# MainProcessor.net
KiCad netlist of a schematic drawn in Altium Designer
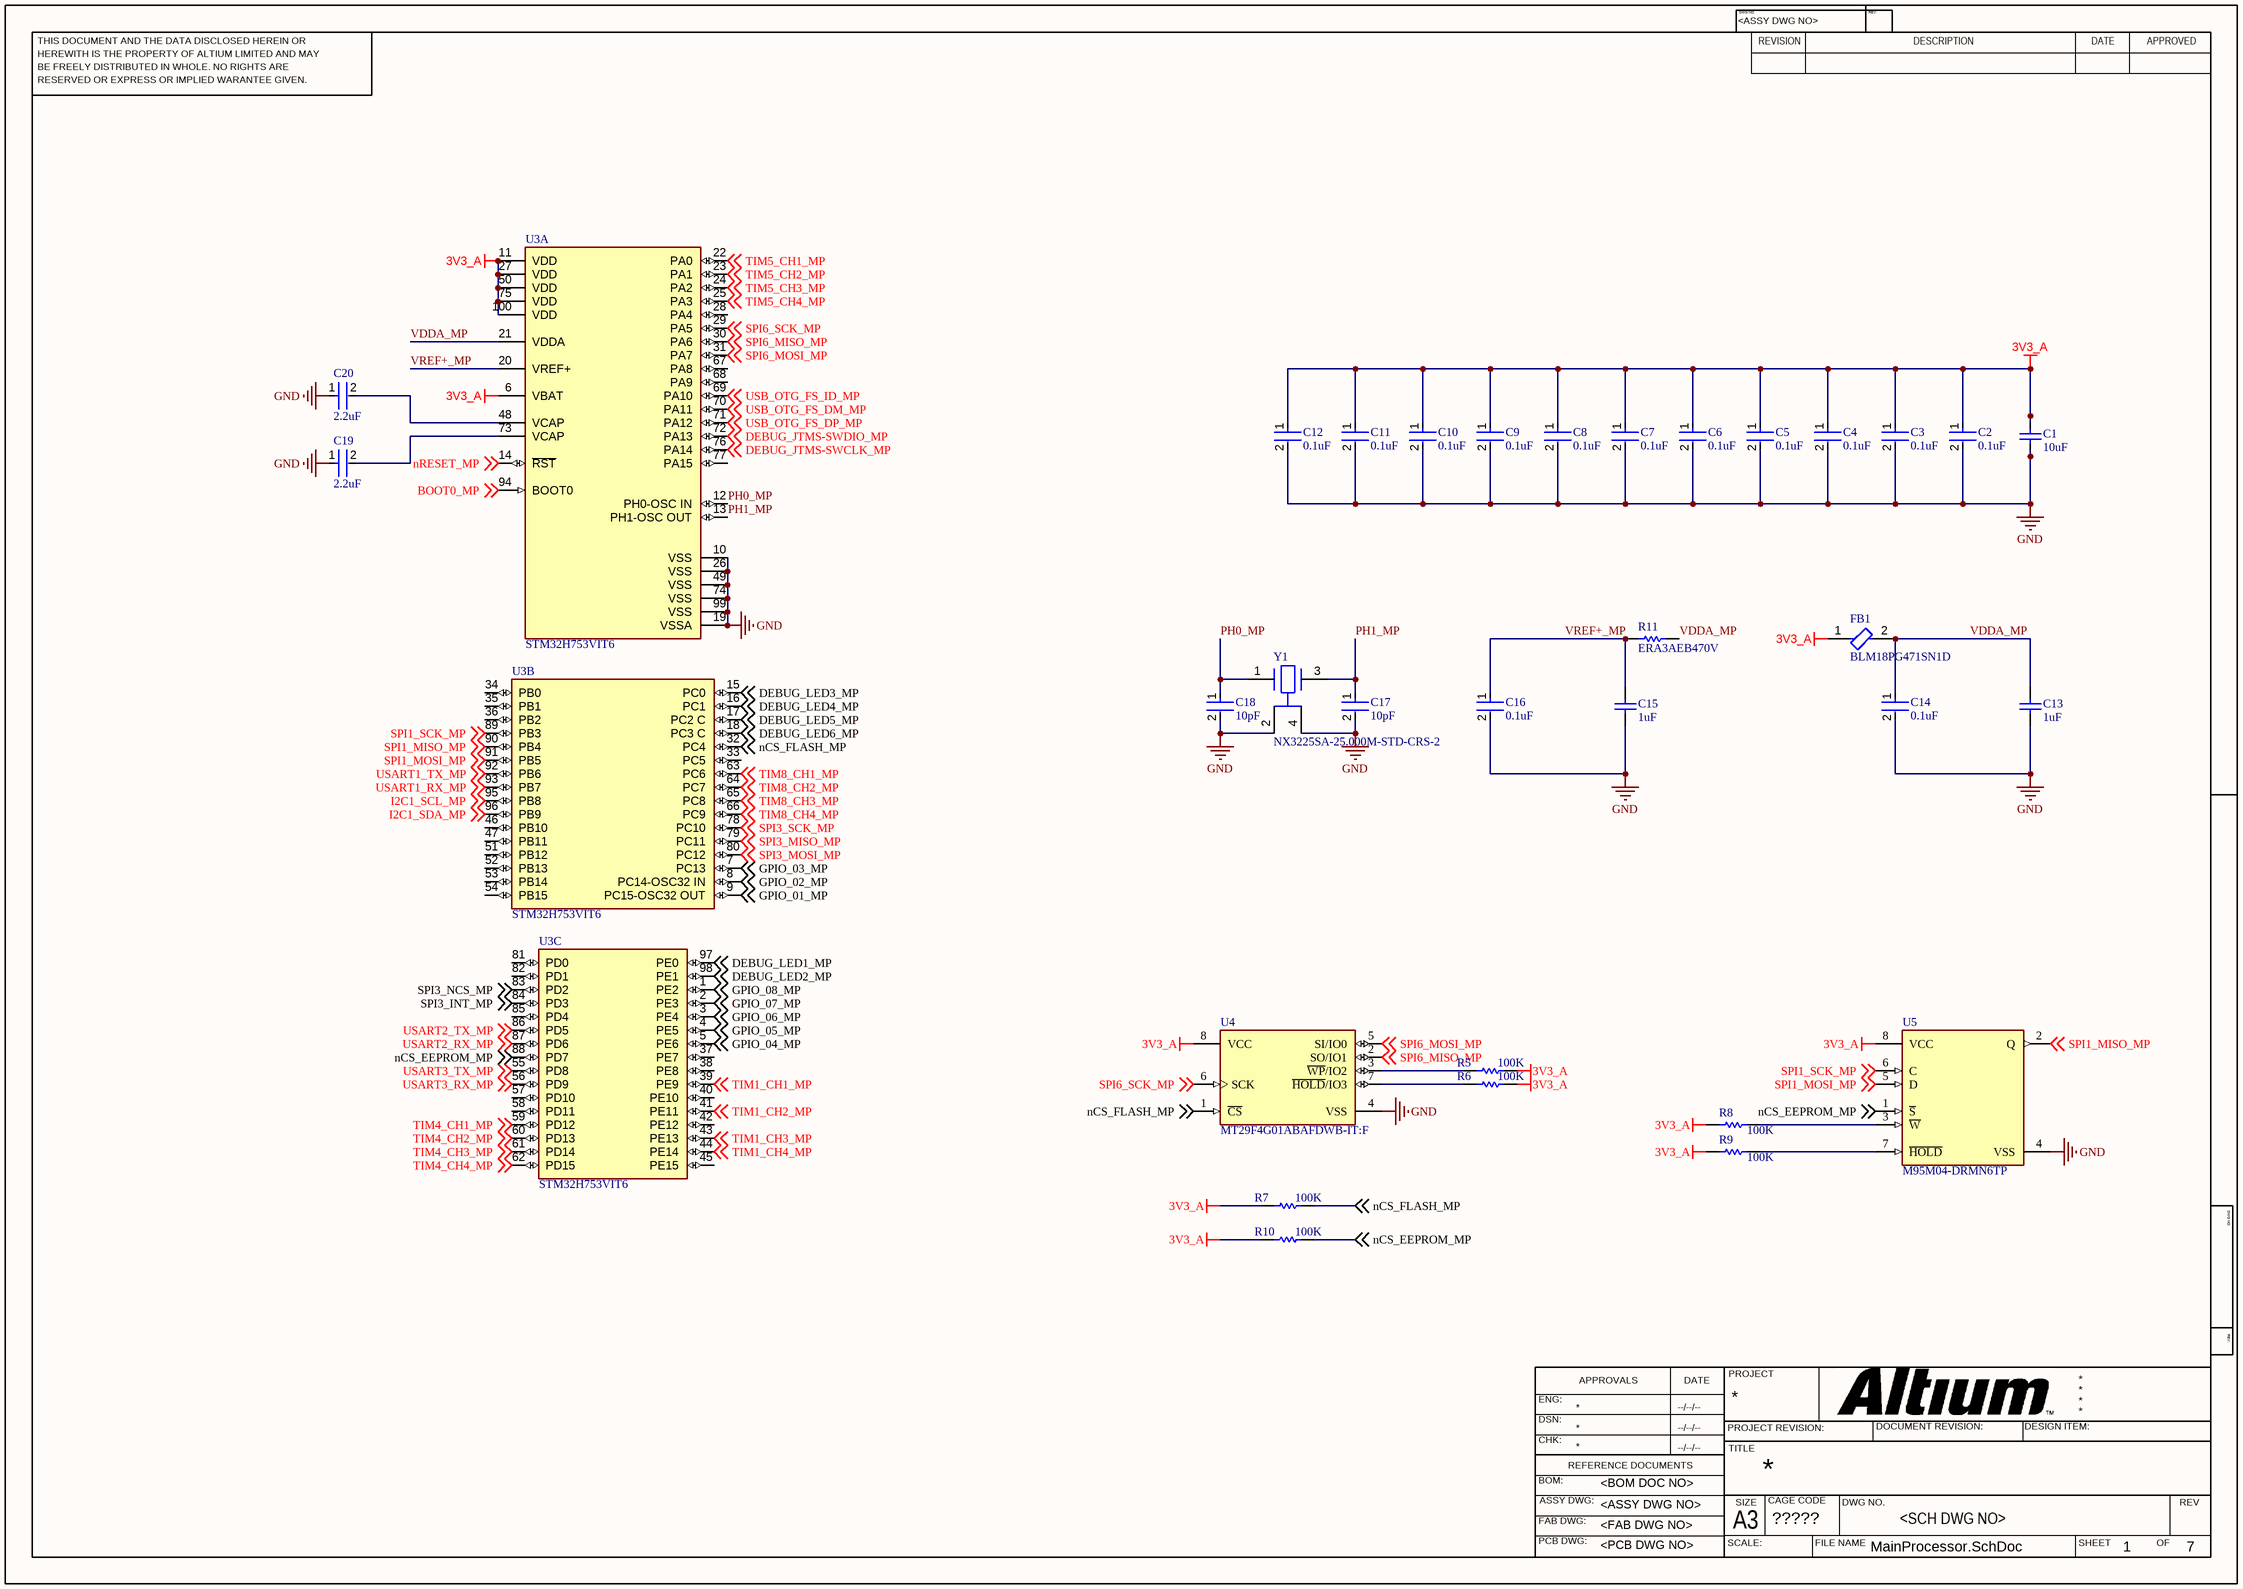
[diagram p0: MainProcessor.SchDoc]

(export (version "E")
  (design (tool "Eeschema 10.0.6"))
  (components
    (comp (ref "C1")
      (value "10uF")
      (footprint "CAPC2013X145X50LL20T25")
      (fields (field (name "MANUFACTURER") "Kemet") (field (name "PART NUMBER") "C0805C106K8RACTU"))
      (libsource (lib "Altium Content Vault") (part "CAP"))
    )
    (comp (ref "C2")
      (value "0.1uF")
      (footprint "FP-C0603C-CF-MFG")
      (description "CAP CER 0.1UF 50V X7R 0603")
      (fields (field (name "TOLERANCE") "0.1") (field (name "MANUFACTURER") "KEMET"))
      (libsource (lib "Altium Content Vault") (part "b4654b650e69147ec39a6b967a45e02"))
    )
    (comp (ref "C3")
      (value "0.1uF")
      (footprint "FP-C0603C-CF-MFG")
      (description "CAP CER 0.1UF 50V X7R 0603")
      (fields (field (name "TOLERANCE") "0.1") (field (name "MANUFACTURER") "KEMET"))
      (libsource (lib "Altium Content Vault") (part "b4654b650e69147ec39a6b967a45e02"))
    )
    (comp (ref "C4")
      (value "0.1uF")
      (footprint "FP-C0603C-CF-MFG")
      (description "CAP CER 0.1UF 50V X7R 0603")
      (fields (field (name "TOLERANCE") "0.1") (field (name "MANUFACTURER") "KEMET"))
      (libsource (lib "Altium Content Vault") (part "b4654b650e69147ec39a6b967a45e02"))
    )
    (comp (ref "C5")
      (value "0.1uF")
      (footprint "FP-C0603C-CF-MFG")
      (description "CAP CER 0.1UF 50V X7R 0603")
      (fields (field (name "TOLERANCE") "0.1") (field (name "MANUFACTURER") "KEMET"))
      (libsource (lib "Altium Content Vault") (part "b4654b650e69147ec39a6b967a45e02"))
    )
    (comp (ref "C6")
      (value "0.1uF")
      (footprint "FP-C0603C-CF-MFG")
      (description "CAP CER 0.1UF 50V X7R 0603")
      (fields (field (name "TOLERANCE") "0.1") (field (name "MANUFACTURER") "KEMET"))
      (libsource (lib "Altium Content Vault") (part "b4654b650e69147ec39a6b967a45e02"))
    )
    (comp (ref "C7")
      (value "0.1uF")
      (footprint "FP-C0603C-CF-MFG")
      (description "CAP CER 0.1UF 50V X7R 0603")
      (fields (field (name "TOLERANCE") "0.1") (field (name "MANUFACTURER") "KEMET"))
      (libsource (lib "Altium Content Vault") (part "b4654b650e69147ec39a6b967a45e02"))
    )
    (comp (ref "C8")
      (value "0.1uF")
      (footprint "FP-C0603C-CF-MFG")
      (description "CAP CER 0.1UF 50V X7R 0603")
      (fields (field (name "TOLERANCE") "0.1") (field (name "MANUFACTURER") "KEMET"))
      (libsource (lib "Altium Content Vault") (part "b4654b650e69147ec39a6b967a45e02"))
    )
    (comp (ref "C9")
      (value "0.1uF")
      (footprint "FP-C0603C-CF-MFG")
      (description "CAP CER 0.1UF 50V X7R 0603")
      (fields (field (name "TOLERANCE") "0.1") (field (name "MANUFACTURER") "KEMET"))
      (libsource (lib "Altium Content Vault") (part "b4654b650e69147ec39a6b967a45e02"))
    )
    (comp (ref "C10")
      (value "0.1uF")
      (footprint "FP-C0603C-CF-MFG")
      (description "CAP CER 0.1UF 50V X7R 0603")
      (fields (field (name "TOLERANCE") "0.1") (field (name "MANUFACTURER") "KEMET"))
      (libsource (lib "Altium Content Vault") (part "b4654b650e69147ec39a6b967a45e02"))
    )
    (comp (ref "C11")
      (value "0.1uF")
      (footprint "FP-C0603C-CF-MFG")
      (description "CAP CER 0.1UF 50V X7R 0603")
      (fields (field (name "TOLERANCE") "0.1") (field (name "MANUFACTURER") "KEMET"))
      (libsource (lib "Altium Content Vault") (part "b4654b650e69147ec39a6b967a45e02"))
    )
    (comp (ref "C12")
      (value "0.1uF")
      (footprint "FP-C0603C-CF-MFG")
      (description "CAP CER 0.1UF 50V X7R 0603")
      (fields (field (name "TOLERANCE") "0.1") (field (name "MANUFACTURER") "KEMET"))
      (libsource (lib "Altium Content Vault") (part "b4654b650e69147ec39a6b967a45e02"))
    )
    (comp (ref "C13")
      (value "1uF")
      (footprint "CAPC1608X90X35LL15T15")
      (fields (field (name "MANUFACTURER") "Kemet") (field (name "PART NUMBER") "C0603C105K4RACTU"))
      (libsource (lib "Altium Content Vault") (part "CAP"))
    )
    (comp (ref "C14")
      (value "0.1uF")
      (footprint "FP-C0603C-CF-MFG")
      (description "CAP CER 0.1UF 50V X7R 0603")
      (fields (field (name "TOLERANCE") "0.1") (field (name "MANUFACTURER") "KEMET"))
      (libsource (lib "Altium Content Vault") (part "b4654b650e69147ec39a6b967a45e02"))
    )
    (comp (ref "C15")
      (value "1uF")
      (footprint "CAPC1608X90X35LL15T15")
      (fields (field (name "MANUFACTURER") "Kemet") (field (name "PART NUMBER") "C0603C105K4RACTU"))
      (libsource (lib "Altium Content Vault") (part "CAP"))
    )
    (comp (ref "C16")
      (value "0.1uF")
      (footprint "FP-C0603C-CF-MFG")
      (description "CAP CER 0.1UF 50V X7R 0603")
      (fields (field (name "TOLERANCE") "0.1") (field (name "MANUFACTURER") "KEMET"))
      (libsource (lib "Altium Content Vault") (part "b4654b650e69147ec39a6b967a45e02"))
    )
    (comp (ref "C17")
      (value "10pF")
      (footprint "FP-C0603C-CF-MFG")
      (description "CAP CER 10PF 50V NP0 0603")
      (fields (field (name "MANUFACTURER") "KEMET") (field (name "TOLERANCE") "0.25 pF"))
      (libsource (lib "Altium Content Vault") (part "b4654b650e69147ec39a6b967a45e02"))
    )
    (comp (ref "C18")
      (value "10pF")
      (footprint "FP-C0603C-CF-MFG")
      (description "CAP CER 10PF 50V NP0 0603")
      (fields (field (name "MANUFACTURER") "KEMET") (field (name "TOLERANCE") "0.25 pF"))
      (libsource (lib "Altium Content Vault") (part "b4654b650e69147ec39a6b967a45e02"))
    )
    (comp (ref "C19")
      (value "2.2uF")
      (footprint "FP-GRM188-0_1-e0_2_0_5-MFG")
      (description "Chip Multilayer Ceramic Capacitors for General Purpose, 0603, 2.2uF, X7R, 15%, 10%, 10V")
      (fields (field (name "VOLTAGE") "10V") (field (name "TOLERANCE") "10%"))
      (libsource (lib "Altium Content Vault") (part "11868f565c42a9108669ba33697ecf6"))
    )
    (comp (ref "C20")
      (value "2.2uF")
      (footprint "FP-GRM188-0_1-e0_2_0_5-MFG")
      (description "Chip Multilayer Ceramic Capacitors for General Purpose, 0603, 2.2uF, X7R, 15%, 10%, 10V")
      (fields (field (name "VOLTAGE") "10V") (field (name "TOLERANCE") "10%"))
      (libsource (lib "Altium Content Vault") (part "11868f565c42a9108669ba33697ecf6"))
    )
    (comp (ref "FB1")
      (value "BLM18PG471SN1D")
      (footprint "FP-BLM18-0_15-t0_8-MFG")
      (description "Chip Ferrite Bead, 0603, 470Ω @ 100MHz, 0.2Ω, 25%, 1A")
      (fields (field (name "TOLERANCE") "25%"))
      (libsource (lib "Altium Content Vault") (part "5f30dd21d616792df468990f7003faa"))
    )
    (comp (ref "R5")
      (value "100K")
      (footprint "RESC1608X55X30ML20T10")
      (fields (field (name "PART NUMBER") "RK73B1JTTD104J") (field (name "MANUFACTURER") "KOA Speer"))
      (libsource (lib "Altium Content Vault") (part "RES"))
    )
    (comp (ref "R6")
      (value "100K")
      (footprint "RESC1608X55X30ML20T10")
      (fields (field (name "PART NUMBER") "RK73B1JTTD104J") (field (name "MANUFACTURER") "KOA Speer"))
      (libsource (lib "Altium Content Vault") (part "RES"))
    )
    (comp (ref "R7")
      (value "100K")
      (footprint "RESC1608X55X30ML20T10")
      (fields (field (name "PART NUMBER") "RK73B1JTTD104J") (field (name "MANUFACTURER") "KOA Speer"))
      (libsource (lib "Altium Content Vault") (part "RES"))
    )
    (comp (ref "R8")
      (value "100K")
      (footprint "RESC1608X55X30ML20T10")
      (fields (field (name "PART NUMBER") "RK73B1JTTD104J") (field (name "MANUFACTURER") "KOA Speer"))
      (libsource (lib "Altium Content Vault") (part "RES"))
    )
    (comp (ref "R9")
      (value "100K")
      (footprint "RESC1608X55X30ML20T10")
      (fields (field (name "PART NUMBER") "RK73B1JTTD104J") (field (name "MANUFACTURER") "KOA Speer"))
      (libsource (lib "Altium Content Vault") (part "RES"))
    )
    (comp (ref "R10")
      (value "100K")
      (footprint "RESC1608X55X30ML20T10")
      (fields (field (name "PART NUMBER") "RK73B1JTTD104J") (field (name "MANUFACTURER") "KOA Speer"))
      (libsource (lib "Altium Content Vault") (part "RES"))
    )
    (comp (ref "R11")
      (value "ERA3AEB470V")
      (footprint "RESC1608X55X30NL20T20")
      (fields (field (name "MANUFACTURER") "Panasonic"))
      (libsource (lib "Altium Content Vault") (part "RES"))
    )
    (comp (ref "U3")
      (value "STM32H753VIT6")
      (footprint "FP-LQFP100-1L-MFG")
      (description "LQFP 100 14X14X1.4")
      (fields
        (field (name "OCTOPART") "https://octopart.com/stm32h753vit6-stmicroelectronics-87879769")
        (field (name "MANUFACTURER") "STMicroelectronics")
      )
      (libsource (lib "Altium Content Vault") (part "0d804454ec25a714beb1806164230ed"))
    )
    (comp (ref "U4")
      (value "MT29F4G01ABAFDWB-IT:F")
      (footprint "FP-WB-IPC_B")
      (description "IC FLASH 4GBIT SPI UPDFN")
      (libsource (lib "Altium Content Vault") (part "2a22d8121842150c115fe802c55be1a"))
    )
    (comp (ref "U5")
      (value "M95M04-DRMN6TP")
      (footprint "FP-SO8N-SO-A-IPC_C")
      (description "STANDARD SERIAL EEPROM")
      (libsource (lib "Altium Content Vault") (part "c55af301368cfa6937ebbf8cb00c05d"))
    )
    (comp (ref "Y1")
      (value "NX3225SA-25.000M-STD-CRS-2")
      (footprint "FP-NX3225SA-MFG")
      (description "CRYSTAL 25.0000MHZ 8PF SMD")
      (fields
        (field (name "OCTOPART") "https://octopart.com/nx3225sa-25.000m-std-crs-2-ndk-51374293")
        (field (name "MANUFACTURER") "NDK")
      )
      (libsource (lib "Altium Content Vault") (part "2e6e5a9c86ccbddb5e6335a7c0ff6ff"))
    )
  )
  (nets
    (net (code "1") (name "/PH0_MP") (class "Default")
      (node (ref "C18") (pin "1") (pinfunction "1_1") (pintype "passive"))
      (node (ref "U3") (pin "12") (pinfunction "PH0-OSC_IN_12") (pintype "bidirectional"))
      (node (ref "Y1") (pin "1") (pinfunction "1_1") (pintype "passive"))
    )
    (net (code "2") (name "/PH1_MP") (class "Default")
      (node (ref "C17") (pin "1") (pinfunction "1_1") (pintype "passive"))
      (node (ref "U3") (pin "13") (pinfunction "PH1-OSC_OUT_13") (pintype "bidirectional"))
      (node (ref "Y1") (pin "3") (pinfunction "3_3") (pintype "passive"))
    )
    (net (code "3") (name "/VDDA_MP") (class "Default")
      (node (ref "C13") (pin "1") (pinfunction "1_1") (pintype "passive"))
      (node (ref "C14") (pin "1") (pinfunction "1_1") (pintype "passive"))
      (node (ref "FB1") (pin "2") (pinfunction "2_2") (pintype "passive"))
      (node (ref "R11") (pin "2") (pinfunction "2_2") (pintype "passive"))
      (node (ref "U3") (pin "21") (pinfunction "VDDA_21") (pintype "power_in"))
    )
    (net (code "4") (name "/VREF+_MP") (class "Default")
      (node (ref "C15") (pin "1") (pinfunction "1_1") (pintype "passive"))
      (node (ref "C16") (pin "1") (pinfunction "1_1") (pintype "passive"))
      (node (ref "R11") (pin "1") (pinfunction "1_1") (pintype "passive"))
      (node (ref "U3") (pin "20") (pinfunction "VREF+_20") (pintype "power_in"))
    )
    (net (code "5") (name "3V3_A") (class "Default")
      (node (ref "C1") (pin "1") (pinfunction "1_1") (pintype "passive"))
      (node (ref "C10") (pin "1") (pinfunction "1_1") (pintype "passive"))
      (node (ref "C11") (pin "1") (pinfunction "1_1") (pintype "passive"))
      (node (ref "C12") (pin "1") (pinfunction "1_1") (pintype "passive"))
      (node (ref "C2") (pin "1") (pinfunction "1_1") (pintype "passive"))
      (node (ref "C3") (pin "1") (pinfunction "1_1") (pintype "passive"))
      (node (ref "C4") (pin "1") (pinfunction "1_1") (pintype "passive"))
      (node (ref "C5") (pin "1") (pinfunction "1_1") (pintype "passive"))
      (node (ref "C6") (pin "1") (pinfunction "1_1") (pintype "passive"))
      (node (ref "C7") (pin "1") (pinfunction "1_1") (pintype "passive"))
      (node (ref "C8") (pin "1") (pinfunction "1_1") (pintype "passive"))
      (node (ref "C9") (pin "1") (pinfunction "1_1") (pintype "passive"))
      (node (ref "FB1") (pin "1") (pinfunction "1_1") (pintype "passive"))
      (node (ref "R10") (pin "2") (pinfunction "2_2") (pintype "passive"))
      (node (ref "R5") (pin "2") (pinfunction "2_2") (pintype "passive"))
      (node (ref "R6") (pin "2") (pinfunction "2_2") (pintype "passive"))
      (node (ref "R7") (pin "2") (pinfunction "2_2") (pintype "passive"))
      (node (ref "R8") (pin "2") (pinfunction "2_2") (pintype "passive"))
      (node (ref "R9") (pin "2") (pinfunction "2_2") (pintype "passive"))
      (node (ref "U3") (pin "100") (pinfunction "VDD_100") (pintype "power_in"))
      (node (ref "U3") (pin "11") (pinfunction "VDD_11") (pintype "power_in"))
      (node (ref "U3") (pin "27") (pinfunction "VDD_27") (pintype "power_in"))
      (node (ref "U3") (pin "50") (pinfunction "VDD_50") (pintype "power_in"))
      (node (ref "U3") (pin "6") (pinfunction "VBAT_6") (pintype "power_in"))
      (node (ref "U3") (pin "75") (pinfunction "VDD_75") (pintype "power_in"))
      (node (ref "U4") (pin "8") (pinfunction "VCC_8") (pintype "power_in"))
      (node (ref "U5") (pin "8") (pinfunction "VCC_8") (pintype "power_in"))
    )
    (net (code "6") (name "BOOT0_MP") (class "Default")
      (node (ref "U3") (pin "94") (pinfunction "BOOT0_94") (pintype "input"))
    )
    (net (code "7") (name "DEBUG_JTMS-SWCLK_MP") (class "Default")
      (node (ref "U3") (pin "76") (pinfunction "PA14_76") (pintype "bidirectional"))
    )
    (net (code "8") (name "DEBUG_JTMS-SWDIO_MP") (class "Default")
      (node (ref "U3") (pin "72") (pinfunction "PA13_72") (pintype "bidirectional"))
    )
    (net (code "9") (name "DEBUG_LED1_MP") (class "Default")
      (node (ref "U3") (pin "97") (pinfunction "PE0_97") (pintype "bidirectional"))
    )
    (net (code "10") (name "DEBUG_LED2_MP") (class "Default")
      (node (ref "U3") (pin "98") (pinfunction "PE1_98") (pintype "bidirectional"))
    )
    (net (code "11") (name "DEBUG_LED3_MP") (class "Default")
      (node (ref "U3") (pin "15") (pinfunction "PC0_15") (pintype "bidirectional"))
    )
    (net (code "12") (name "DEBUG_LED4_MP") (class "Default")
      (node (ref "U3") (pin "16") (pinfunction "PC1_16") (pintype "bidirectional"))
    )
    (net (code "13") (name "DEBUG_LED5_MP") (class "Default")
      (node (ref "U3") (pin "17") (pinfunction "PC2_C_17") (pintype "bidirectional"))
    )
    (net (code "14") (name "DEBUG_LED6_MP") (class "Default")
      (node (ref "U3") (pin "18") (pinfunction "PC3_C_18") (pintype "bidirectional"))
    )
    (net (code "15") (name "GND") (class "Default")
      (node (ref "C1") (pin "2") (pinfunction "2_2") (pintype "passive"))
      (node (ref "C10") (pin "2") (pinfunction "2_2") (pintype "passive"))
      (node (ref "C11") (pin "2") (pinfunction "2_2") (pintype "passive"))
      (node (ref "C12") (pin "2") (pinfunction "2_2") (pintype "passive"))
      (node (ref "C13") (pin "2") (pinfunction "2_2") (pintype "passive"))
      (node (ref "C14") (pin "2") (pinfunction "2_2") (pintype "passive"))
      (node (ref "C15") (pin "2") (pinfunction "2_2") (pintype "passive"))
      (node (ref "C16") (pin "2") (pinfunction "2_2") (pintype "passive"))
      (node (ref "C17") (pin "2") (pinfunction "2_2") (pintype "passive"))
      (node (ref "C18") (pin "2") (pinfunction "2_2") (pintype "passive"))
      (node (ref "C19") (pin "1") (pinfunction "1_1") (pintype "passive"))
      (node (ref "C2") (pin "2") (pinfunction "2_2") (pintype "passive"))
      (node (ref "C20") (pin "1") (pinfunction "1_1") (pintype "passive"))
      (node (ref "C3") (pin "2") (pinfunction "2_2") (pintype "passive"))
      (node (ref "C4") (pin "2") (pinfunction "2_2") (pintype "passive"))
      (node (ref "C5") (pin "2") (pinfunction "2_2") (pintype "passive"))
      (node (ref "C6") (pin "2") (pinfunction "2_2") (pintype "passive"))
      (node (ref "C7") (pin "2") (pinfunction "2_2") (pintype "passive"))
      (node (ref "C8") (pin "2") (pinfunction "2_2") (pintype "passive"))
      (node (ref "C9") (pin "2") (pinfunction "2_2") (pintype "passive"))
      (node (ref "U3") (pin "10") (pinfunction "VSS_10") (pintype "power_in"))
      (node (ref "U3") (pin "19") (pinfunction "VSSA_19") (pintype "power_in"))
      (node (ref "U3") (pin "26") (pinfunction "VSS_26") (pintype "power_in"))
      (node (ref "U3") (pin "49") (pinfunction "VSS_49") (pintype "power_in"))
      (node (ref "U3") (pin "74") (pinfunction "VSS_74") (pintype "power_in"))
      (node (ref "U3") (pin "99") (pinfunction "VSS_99") (pintype "power_in"))
      (node (ref "U4") (pin "4") (pinfunction "VSS_4") (pintype "power_in"))
      (node (ref "U5") (pin "4") (pinfunction "VSS_4") (pintype "power_in"))
      (node (ref "Y1") (pin "2") (pinfunction "GND_2") (pintype "power_in"))
      (node (ref "Y1") (pin "4") (pinfunction "GND_4") (pintype "power_in"))
    )
    (net (code "16") (name "GPIO_01_MP") (class "Default")
      (node (ref "U3") (pin "9") (pinfunction "PC15-OSC32_OUT_9") (pintype "bidirectional"))
    )
    (net (code "17") (name "GPIO_02_MP") (class "Default")
      (node (ref "U3") (pin "8") (pinfunction "PC14-OSC32_IN_8") (pintype "bidirectional"))
    )
    (net (code "18") (name "GPIO_03_MP") (class "Default")
      (node (ref "U3") (pin "7") (pinfunction "PC13_7") (pintype "bidirectional"))
    )
    (net (code "19") (name "GPIO_04_MP") (class "Default")
      (node (ref "U3") (pin "5") (pinfunction "PE6_5") (pintype "bidirectional"))
    )
    (net (code "20") (name "GPIO_05_MP") (class "Default")
      (node (ref "U3") (pin "4") (pinfunction "PE5_4") (pintype "bidirectional"))
    )
    (net (code "21") (name "GPIO_06_MP") (class "Default")
      (node (ref "U3") (pin "3") (pinfunction "PE4_3") (pintype "bidirectional"))
    )
    (net (code "22") (name "GPIO_07_MP") (class "Default")
      (node (ref "U3") (pin "2") (pinfunction "PE3_2") (pintype "bidirectional"))
    )
    (net (code "23") (name "GPIO_08_MP") (class "Default")
      (node (ref "U3") (pin "1") (pinfunction "PE2_1") (pintype "bidirectional"))
    )
    (net (code "24") (name "I2C1_SCL_MP") (class "Default")
      (node (ref "U3") (pin "95") (pinfunction "PB8_95") (pintype "bidirectional"))
    )
    (net (code "25") (name "I2C1_SDA_MP") (class "Default")
      (node (ref "U3") (pin "96") (pinfunction "PB9_96") (pintype "bidirectional"))
    )
    (net (code "26") (name "Net-(C19-Pad2)") (class "Default")
      (node (ref "C19") (pin "2") (pinfunction "2_2") (pintype "passive"))
      (node (ref "U3") (pin "73") (pinfunction "VCAP_73") (pintype "power_in"))
    )
    (net (code "27") (name "Net-(C20-Pad2)") (class "Default")
      (node (ref "C20") (pin "2") (pinfunction "2_2") (pintype "passive"))
      (node (ref "U3") (pin "48") (pinfunction "VCAP_48") (pintype "power_in"))
    )
    (net (code "28") (name "Net-(U4-~{HOLD}{slash}IO3)") (class "Default")
      (node (ref "R6") (pin "1") (pinfunction "1_1") (pintype "passive"))
      (node (ref "U4") (pin "7") (pinfunction "~{HOLD}/IO3_7") (pintype "bidirectional"))
    )
    (net (code "29") (name "Net-(U4-~{WP}{slash}IO2)") (class "Default")
      (node (ref "R5") (pin "1") (pinfunction "1_1") (pintype "passive"))
      (node (ref "U4") (pin "3") (pinfunction "~{WP}/IO2_3") (pintype "bidirectional"))
    )
    (net (code "30") (name "Net-(U5-~{HOLD})") (class "Default")
      (node (ref "R9") (pin "1") (pinfunction "1_1") (pintype "passive"))
      (node (ref "U5") (pin "7") (pinfunction "~{HOLD}_7") (pintype "input"))
    )
    (net (code "31") (name "Net-(U5-~{W})") (class "Default")
      (node (ref "R8") (pin "1") (pinfunction "1_1") (pintype "passive"))
      (node (ref "U5") (pin "3") (pinfunction "~{W}_3") (pintype "input"))
    )
    (net (code "32") (name "SPI1_MISO_MP") (class "Default")
      (node (ref "U3") (pin "90") (pinfunction "PB4_90") (pintype "bidirectional"))
      (node (ref "U5") (pin "2") (pinfunction "Q_2") (pintype "output"))
    )
    (net (code "33") (name "SPI1_MOSI_MP") (class "Default")
      (node (ref "U3") (pin "91") (pinfunction "PB5_91") (pintype "bidirectional"))
      (node (ref "U5") (pin "5") (pinfunction "D_5") (pintype "input"))
    )
    (net (code "34") (name "SPI1_SCK_MP") (class "Default")
      (node (ref "U3") (pin "89") (pinfunction "PB3_89") (pintype "bidirectional"))
      (node (ref "U5") (pin "6") (pinfunction "C_6") (pintype "input"))
    )
    (net (code "35") (name "SPI3_INT_MP") (class "Default")
      (node (ref "U3") (pin "84") (pinfunction "PD3_84") (pintype "bidirectional"))
    )
    (net (code "36") (name "SPI3_MISO_MP") (class "Default")
      (node (ref "U3") (pin "79") (pinfunction "PC11_79") (pintype "bidirectional"))
    )
    (net (code "37") (name "SPI3_MOSI_MP") (class "Default")
      (node (ref "U3") (pin "80") (pinfunction "PC12_80") (pintype "bidirectional"))
    )
    (net (code "38") (name "SPI3_NCS_MP") (class "Default")
      (node (ref "U3") (pin "83") (pinfunction "PD2_83") (pintype "bidirectional"))
    )
    (net (code "39") (name "SPI3_SCK_MP") (class "Default")
      (node (ref "U3") (pin "78") (pinfunction "PC10_78") (pintype "bidirectional"))
    )
    (net (code "40") (name "SPI6_MISO_MP") (class "Default")
      (node (ref "U3") (pin "30") (pinfunction "PA6_30") (pintype "bidirectional"))
      (node (ref "U4") (pin "2") (pinfunction "SO/IO1_2") (pintype "bidirectional"))
    )
    (net (code "41") (name "SPI6_MOSI_MP") (class "Default")
      (node (ref "U3") (pin "31") (pinfunction "PA7_31") (pintype "bidirectional"))
      (node (ref "U4") (pin "5") (pinfunction "SI/IO0_5") (pintype "bidirectional"))
    )
    (net (code "42") (name "SPI6_SCK_MP") (class "Default")
      (node (ref "U3") (pin "29") (pinfunction "PA5_29") (pintype "bidirectional"))
      (node (ref "U4") (pin "6") (pinfunction "SCK_6") (pintype "input"))
    )
    (net (code "43") (name "TIM1_CH1_MP") (class "Default")
      (node (ref "U3") (pin "39") (pinfunction "PE9_39") (pintype "bidirectional"))
    )
    (net (code "44") (name "TIM1_CH2_MP") (class "Default")
      (node (ref "U3") (pin "41") (pinfunction "PE11_41") (pintype "bidirectional"))
    )
    (net (code "45") (name "TIM1_CH3_MP") (class "Default")
      (node (ref "U3") (pin "43") (pinfunction "PE13_43") (pintype "bidirectional"))
    )
    (net (code "46") (name "TIM1_CH4_MP") (class "Default")
      (node (ref "U3") (pin "44") (pinfunction "PE14_44") (pintype "bidirectional"))
    )
    (net (code "47") (name "TIM4_CH1_MP") (class "Default")
      (node (ref "U3") (pin "59") (pinfunction "PD12_59") (pintype "bidirectional"))
    )
    (net (code "48") (name "TIM4_CH2_MP") (class "Default")
      (node (ref "U3") (pin "60") (pinfunction "PD13_60") (pintype "bidirectional"))
    )
    (net (code "49") (name "TIM4_CH3_MP") (class "Default")
      (node (ref "U3") (pin "61") (pinfunction "PD14_61") (pintype "bidirectional"))
    )
    (net (code "50") (name "TIM4_CH4_MP") (class "Default")
      (node (ref "U3") (pin "62") (pinfunction "PD15_62") (pintype "bidirectional"))
    )
    (net (code "51") (name "TIM5_CH1_MP") (class "Default")
      (node (ref "U3") (pin "22") (pinfunction "PA0_22") (pintype "bidirectional"))
    )
    (net (code "52") (name "TIM5_CH2_MP") (class "Default")
      (node (ref "U3") (pin "23") (pinfunction "PA1_23") (pintype "bidirectional"))
    )
    (net (code "53") (name "TIM5_CH3_MP") (class "Default")
      (node (ref "U3") (pin "24") (pinfunction "PA2_24") (pintype "bidirectional"))
    )
    (net (code "54") (name "TIM5_CH4_MP") (class "Default")
      (node (ref "U3") (pin "25") (pinfunction "PA3_25") (pintype "bidirectional"))
    )
    (net (code "55") (name "TIM8_CH1_MP") (class "Default")
      (node (ref "U3") (pin "63") (pinfunction "PC6_63") (pintype "bidirectional"))
    )
    (net (code "56") (name "TIM8_CH2_MP") (class "Default")
      (node (ref "U3") (pin "64") (pinfunction "PC7_64") (pintype "bidirectional"))
    )
    (net (code "57") (name "TIM8_CH3_MP") (class "Default")
      (node (ref "U3") (pin "65") (pinfunction "PC8_65") (pintype "bidirectional"))
    )
    (net (code "58") (name "TIM8_CH4_MP") (class "Default")
      (node (ref "U3") (pin "66") (pinfunction "PC9_66") (pintype "bidirectional"))
    )
    (net (code "59") (name "USART1_RX_MP") (class "Default")
      (node (ref "U3") (pin "93") (pinfunction "PB7_93") (pintype "bidirectional"))
    )
    (net (code "60") (name "USART1_TX_MP") (class "Default")
      (node (ref "U3") (pin "92") (pinfunction "PB6_92") (pintype "bidirectional"))
    )
    (net (code "61") (name "USART2_RX_MP") (class "Default")
      (node (ref "U3") (pin "87") (pinfunction "PD6_87") (pintype "bidirectional"))
    )
    (net (code "62") (name "USART2_TX_MP") (class "Default")
      (node (ref "U3") (pin "86") (pinfunction "PD5_86") (pintype "bidirectional"))
    )
    (net (code "63") (name "USART3_RX_MP") (class "Default")
      (node (ref "U3") (pin "56") (pinfunction "PD9_56") (pintype "bidirectional"))
    )
    (net (code "64") (name "USART3_TX_MP") (class "Default")
      (node (ref "U3") (pin "55") (pinfunction "PD8_55") (pintype "bidirectional"))
    )
    (net (code "65") (name "USB_OTG_FS_DM_MP") (class "Default")
      (node (ref "U3") (pin "70") (pinfunction "PA11_70") (pintype "bidirectional"))
    )
    (net (code "66") (name "USB_OTG_FS_DP_MP") (class "Default")
      (node (ref "U3") (pin "71") (pinfunction "PA12_71") (pintype "bidirectional"))
    )
    (net (code "67") (name "USB_OTG_FS_ID_MP") (class "Default")
      (node (ref "U3") (pin "69") (pinfunction "PA10_69") (pintype "bidirectional"))
    )
    (net (code "68") (name "nCS_EEPROM_MP") (class "Default")
      (node (ref "R10") (pin "1") (pinfunction "1_1") (pintype "passive"))
      (node (ref "U3") (pin "88") (pinfunction "PD7_88") (pintype "bidirectional"))
      (node (ref "U5") (pin "1") (pinfunction "~{S}_1") (pintype "input"))
    )
    (net (code "69") (name "nCS_FLASH_MP") (class "Default")
      (node (ref "R7") (pin "1") (pinfunction "1_1") (pintype "passive"))
      (node (ref "U3") (pin "32") (pinfunction "PC4_32") (pintype "bidirectional"))
      (node (ref "U4") (pin "1") (pinfunction "~{CS}_1") (pintype "input"))
    )
    (net (code "70") (name "nRESET_MP") (class "Default")
      (node (ref "U3") (pin "14") (pinfunction "~{RST}_14") (pintype "bidirectional"))
    )
    (net (code "71") (name "unconnected-(U3A-PA4-Pad28)") (class "Default")
      (node (ref "U3") (pin "28") (pinfunction "PA4_28") (pintype "bidirectional"))
    )
    (net (code "72") (name "unconnected-(U3A-PA8-Pad67)") (class "Default")
      (node (ref "U3") (pin "67") (pinfunction "PA8_67") (pintype "bidirectional"))
    )
    (net (code "73") (name "unconnected-(U3A-PA9-Pad68)") (class "Default")
      (node (ref "U3") (pin "68") (pinfunction "PA9_68") (pintype "bidirectional"))
    )
    (net (code "74") (name "unconnected-(U3A-PA15-Pad77)") (class "Default")
      (node (ref "U3") (pin "77") (pinfunction "PA15_77") (pintype "bidirectional"))
    )
    (net (code "75") (name "unconnected-(U3B-PB0-Pad34)") (class "Default")
      (node (ref "U3") (pin "34") (pinfunction "PB0_34") (pintype "bidirectional"))
    )
    (net (code "76") (name "unconnected-(U3B-PB1-Pad35)") (class "Default")
      (node (ref "U3") (pin "35") (pinfunction "PB1_35") (pintype "bidirectional"))
    )
    (net (code "77") (name "unconnected-(U3B-PB2-Pad36)") (class "Default")
      (node (ref "U3") (pin "36") (pinfunction "PB2_36") (pintype "bidirectional"))
    )
    (net (code "78") (name "unconnected-(U3B-PB10-Pad46)") (class "Default")
      (node (ref "U3") (pin "46") (pinfunction "PB10_46") (pintype "bidirectional"))
    )
    (net (code "79") (name "unconnected-(U3B-PB11-Pad47)") (class "Default")
      (node (ref "U3") (pin "47") (pinfunction "PB11_47") (pintype "bidirectional"))
    )
    (net (code "80") (name "unconnected-(U3B-PB12-Pad51)") (class "Default")
      (node (ref "U3") (pin "51") (pinfunction "PB12_51") (pintype "bidirectional"))
    )
    (net (code "81") (name "unconnected-(U3B-PB13-Pad52)") (class "Default")
      (node (ref "U3") (pin "52") (pinfunction "PB13_52") (pintype "bidirectional"))
    )
    (net (code "82") (name "unconnected-(U3B-PB14-Pad53)") (class "Default")
      (node (ref "U3") (pin "53") (pinfunction "PB14_53") (pintype "bidirectional"))
    )
    (net (code "83") (name "unconnected-(U3B-PB15-Pad54)") (class "Default")
      (node (ref "U3") (pin "54") (pinfunction "PB15_54") (pintype "bidirectional"))
    )
    (net (code "84") (name "unconnected-(U3B-PC5-Pad33)") (class "Default")
      (node (ref "U3") (pin "33") (pinfunction "PC5_33") (pintype "bidirectional"))
    )
    (net (code "85") (name "unconnected-(U3C-PD0-Pad81)") (class "Default")
      (node (ref "U3") (pin "81") (pinfunction "PD0_81") (pintype "bidirectional"))
    )
    (net (code "86") (name "unconnected-(U3C-PD1-Pad82)") (class "Default")
      (node (ref "U3") (pin "82") (pinfunction "PD1_82") (pintype "bidirectional"))
    )
    (net (code "87") (name "unconnected-(U3C-PD4-Pad85)") (class "Default")
      (node (ref "U3") (pin "85") (pinfunction "PD4_85") (pintype "bidirectional"))
    )
    (net (code "88") (name "unconnected-(U3C-PD10-Pad57)") (class "Default")
      (node (ref "U3") (pin "57") (pinfunction "PD10_57") (pintype "bidirectional"))
    )
    (net (code "89") (name "unconnected-(U3C-PD11-Pad58)") (class "Default")
      (node (ref "U3") (pin "58") (pinfunction "PD11_58") (pintype "bidirectional"))
    )
    (net (code "90") (name "unconnected-(U3C-PE7-Pad37)") (class "Default")
      (node (ref "U3") (pin "37") (pinfunction "PE7_37") (pintype "bidirectional"))
    )
    (net (code "91") (name "unconnected-(U3C-PE8-Pad38)") (class "Default")
      (node (ref "U3") (pin "38") (pinfunction "PE8_38") (pintype "bidirectional"))
    )
    (net (code "92") (name "unconnected-(U3C-PE10-Pad40)") (class "Default")
      (node (ref "U3") (pin "40") (pinfunction "PE10_40") (pintype "bidirectional"))
    )
    (net (code "93") (name "unconnected-(U3C-PE12-Pad42)") (class "Default")
      (node (ref "U3") (pin "42") (pinfunction "PE12_42") (pintype "bidirectional"))
    )
    (net (code "94") (name "unconnected-(U3C-PE15-Pad45)") (class "Default")
      (node (ref "U3") (pin "45") (pinfunction "PE15_45") (pintype "bidirectional"))
    )
  )
)
